# Hands_free_ControlUnit_V1.net
KiCad netlist of a schematic drawn in Altium Designer
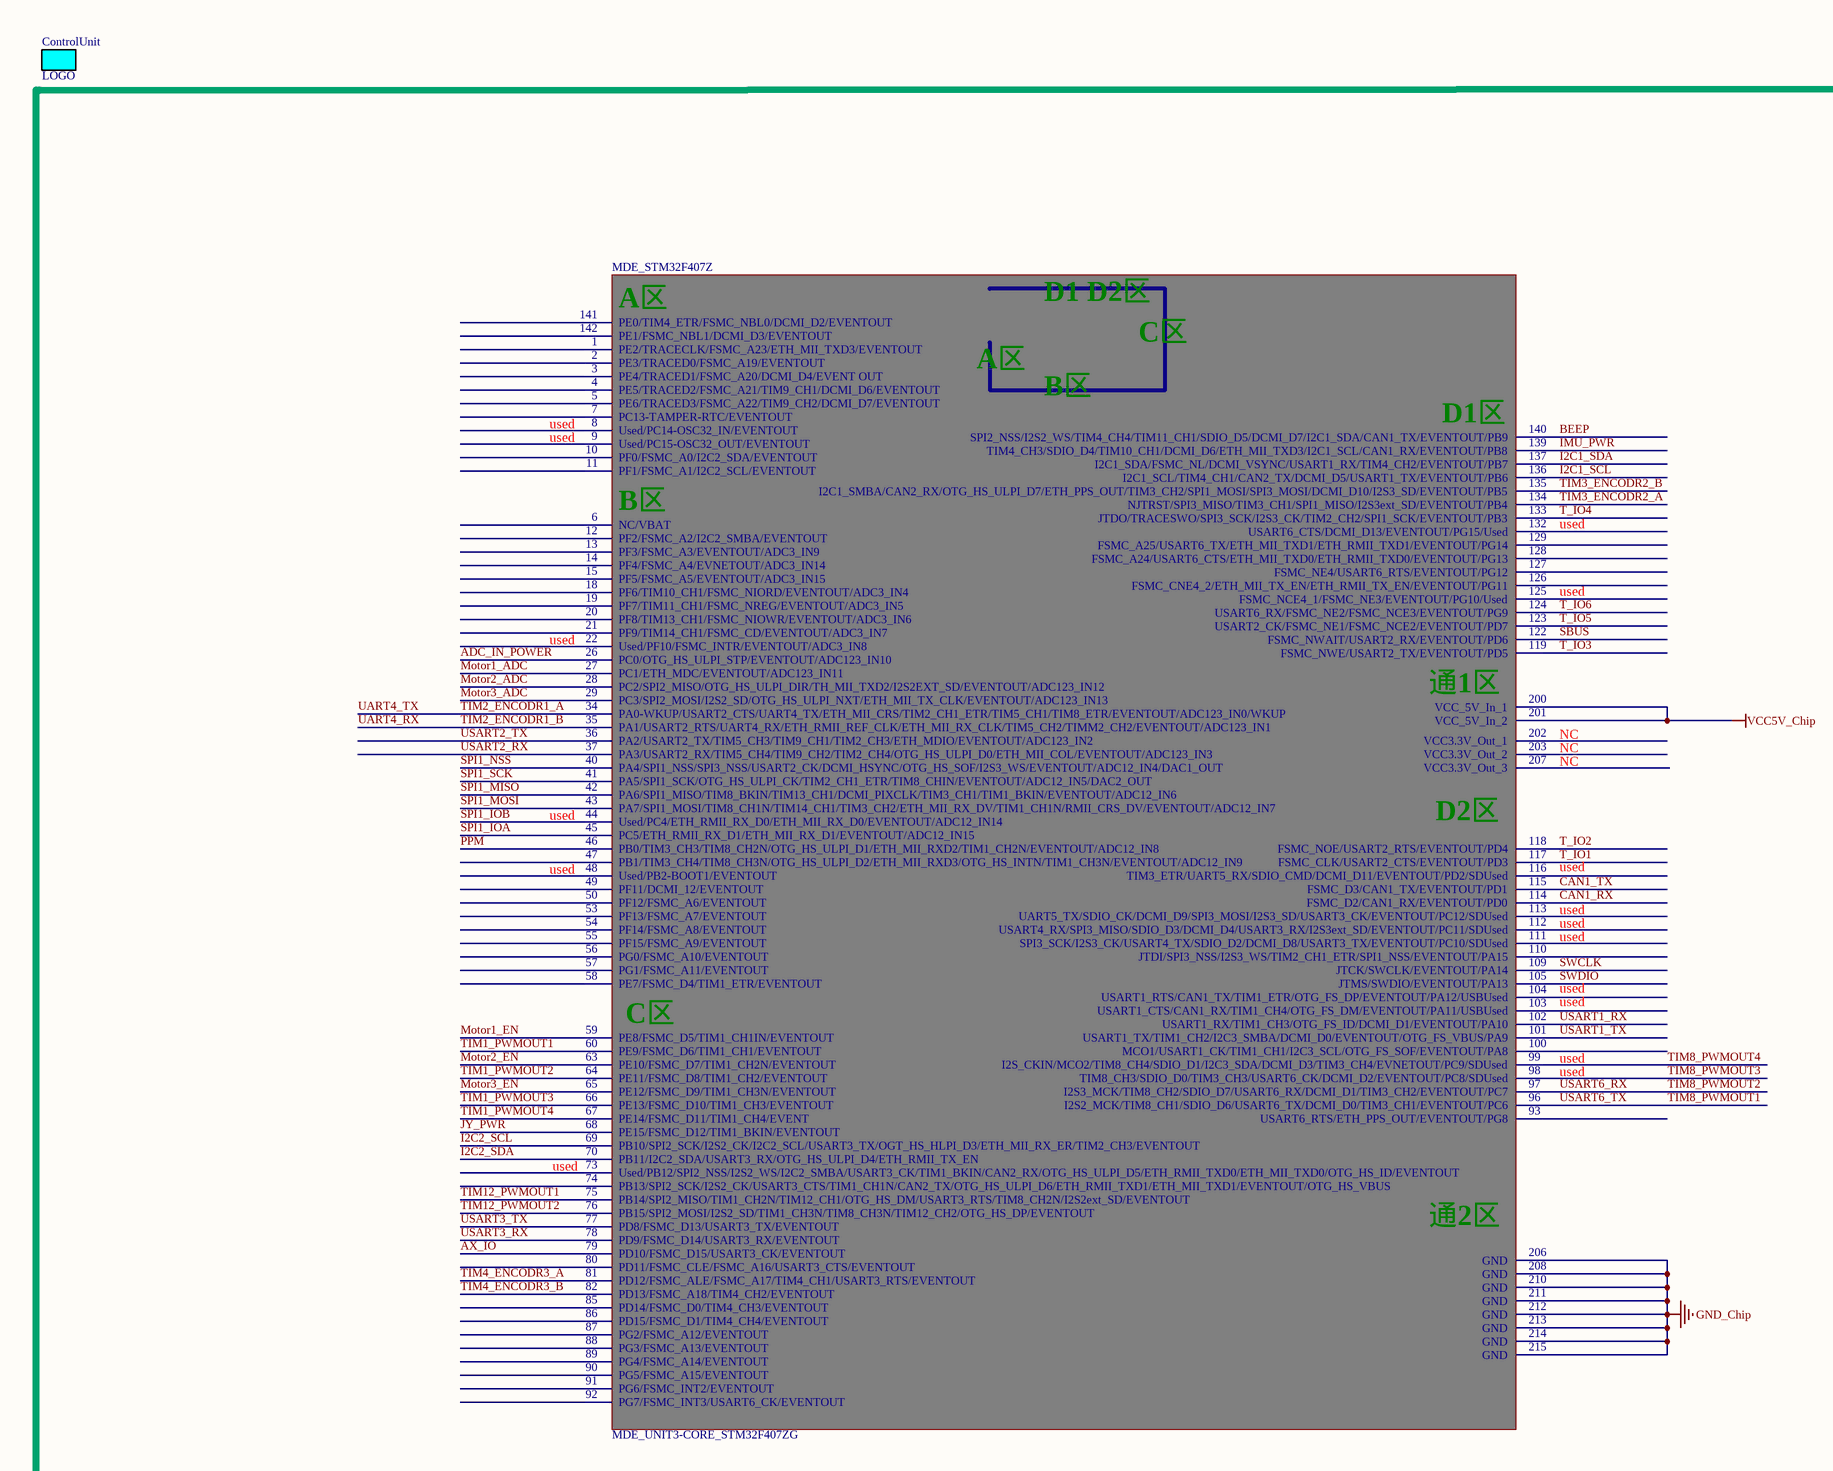
[diagram p0: Hands_free_ControlUnit_V1.SchDoc, top left]
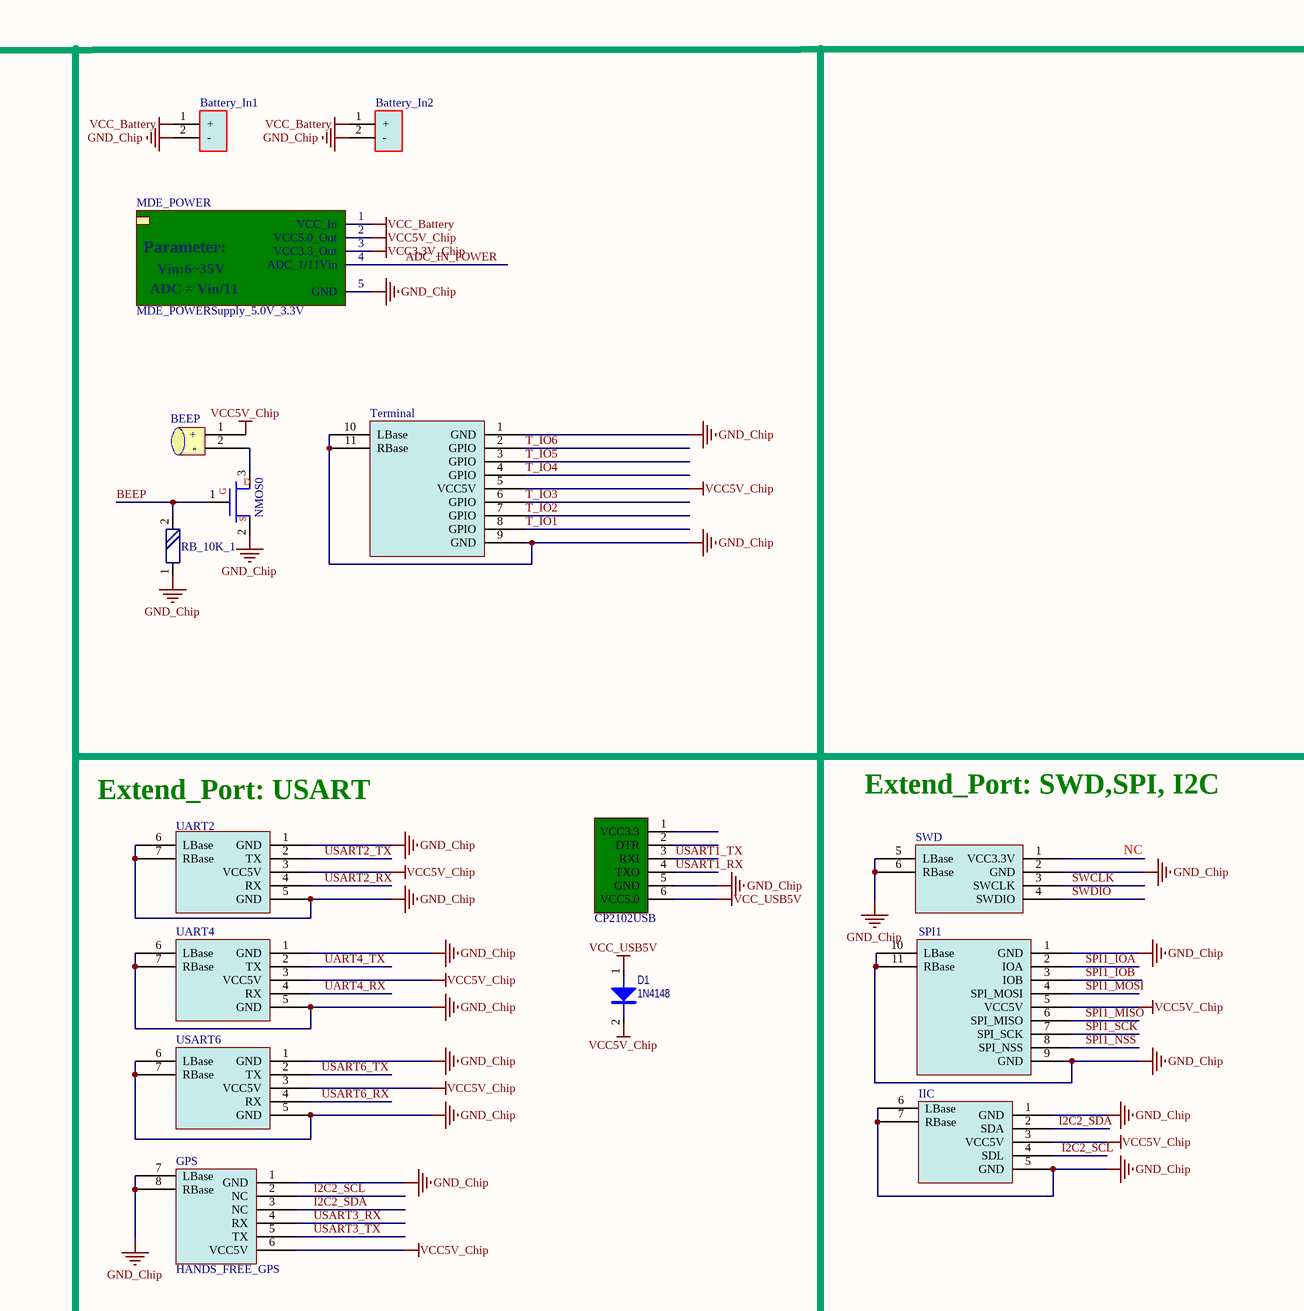
[diagram p1: Hands_free_ControlUnit_V1.SchDoc, top middle]
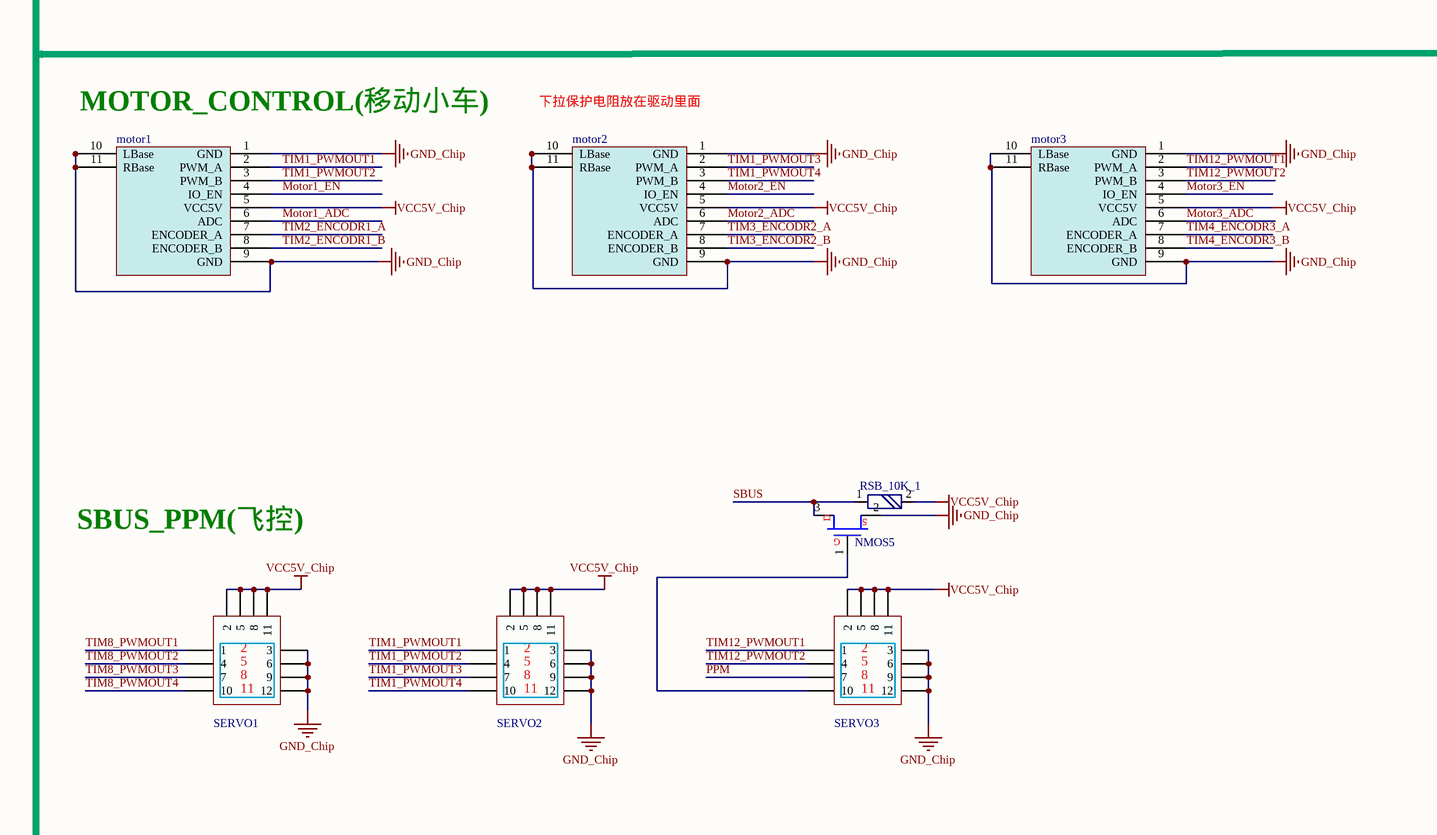
[diagram p2: Hands_free_ControlUnit_V1.SchDoc, bottom left]
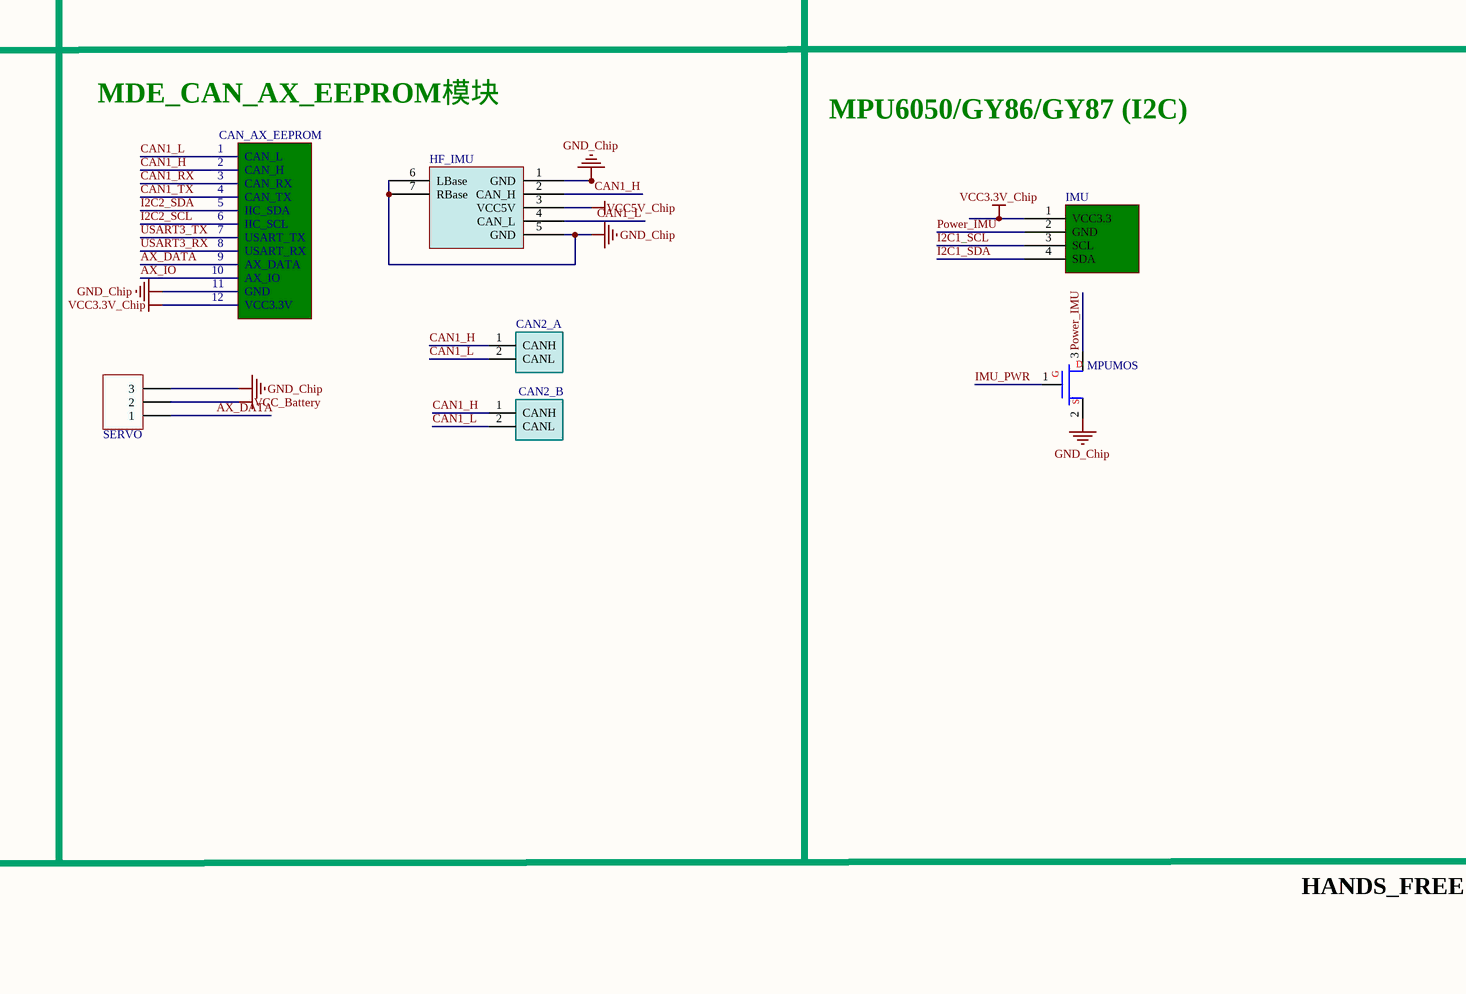
[diagram p3: Hands_free_ControlUnit_V1.SchDoc, bottom middle]
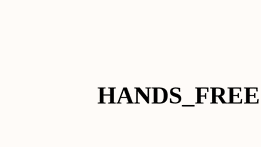
[diagram p4: Hands_free_ControlUnit_V1.SchDoc, bottom right]

(export (version "E")
  (design (tool "Eeschema 10.0.6"))
  (components
    (comp (ref "Battery_In1")
      (value "HDR_Header_Power_2P")
      (footprint "HDR_MOLEX_POWER5557_DH_2P")
      (libsource (lib "HANDS-FREEE-PcbLib-V1.00") (part "HDR_Header_Power_2P"))
    )
    (comp (ref "Battery_In2")
      (value "HDR_Header_Power_2P")
      (footprint "HDR_MOLEX_POWER5557_DH_2P")
      (libsource (lib "HANDS-FREEE-PcbLib-V1.00") (part "HDR_Header_Power_2P"))
    )
    (comp (ref "BEEP")
      (value "ELE_蜂鸣器12*X")
      (footprint "ELE_蜂鸣器_D_12*X")
      (libsource (lib "Hands_free") (part "ELE_蜂鸣器12*X"))
    )
    (comp (ref "CAN2_A")
      (value "HDR_HEADER_CAN_DH_2P")
      (footprint "HDR_MOLEX_CANMX3.0_DH_2P")
      (libsource (lib "Hands_free") (part "HDR_HEADER_CAN_DH_2P"))
    )
    (comp (ref "CAN2_B")
      (value "HDR_HEADER_CAN_DH_2P")
      (footprint "HDR_MOLEX_CANMX3.0_DH_2P")
      (libsource (lib "Hands_free") (part "HDR_HEADER_CAN_DH_2P"))
    )
    (comp (ref "CAN_AX_EEPROM")
      (value "MDE_CAN_AX_EEPROM")
      (footprint "MDE_CAN_AX_EEPROM")
      (libsource (lib "Hands_free") (part "MDE_CAN_AX_EEPROM"))
    )
    (comp (ref "ControlUnit") (value "LOGO") (footprint "LOGO") (libsource (lib "Hands_free") (part "LOGO")))
    (comp (ref "CP2102USB")
      (value "MDE_CP2102-TTLUSB")
      (footprint "MDE_CP2102-TTLUSB_BASE")
      (description "CP2102模块，TTL-USB")
      (libsource (lib "HANDS-FREEE-PcbLib-V1.06") (part "MDE_CP2102-TTLUSB"))
    )
    (comp (ref "D1")
      (value "1N4148")
      (footprint "ELE_D1206")
      (description "二极管")
      (libsource (lib "Hands_free") (part "ELE_Diode"))
    )
    (comp (ref "GPS")
      (value "HANDS_FREE_GPS")
      (footprint "HDR_Molex_PH_1.25_6P")
      (libsource (lib "Hands_free") (part "HANDS_FREE_GPS"))
    )
    (comp (ref "HF_IMU")
      (value "HANDS_FREE_IMU")
      (footprint "HDR_Molex_PH_1.25_5P")
      (libsource (lib "Hands_free") (part "HANDS_FREE_IMU"))
    )
    (comp (ref "IIC")
      (value "HANDS_FREE_IIC")
      (footprint "HDR_Molex_PH_1.25_5P")
      (libsource (lib "Hands_free") (part "HANDS_FREE_IIC"))
    )
    (comp (ref "IMU")
      (value "MDE_GY86_87")
      (footprint "MDE_GY86_GY87_BASE")
      (description "IMU模块")
      (libsource (lib "Hands_free") (part "MDE_GY86_87"))
    )
    (comp (ref "MDE_POWER")
      (value "MDE_POWERSupply_5.0V_3.3V")
      (footprint "MDE_POWERSupply_5.0V_3.3V")
      (libsource (lib "HANDS-FREEE-PcbLib-V1.06") (part "MDE_POWERSupply_5.0V_3.3V"))
    )
    (comp (ref "MDE_STM32F407Z")
      (value "MDE_UNIT3-CORE_STM32F407ZG")
      (footprint "MDE_UNIT3-CORE_STM32F407ZG")
      (libsource (lib "HANDS-FREEE-PcbLib-V1.05") (part "MDE_UNIT3-CORE_STM32F407ZG"))
    )
    (comp (ref "motor1")
      (value "*MOTOR")
      (footprint "HDR_Molex_PH_1.25_9P")
      (libsource (lib "Hands_free") (part "HANDS_FREE_MOTOR"))
    )
    (comp (ref "motor2")
      (value "*MOTOR")
      (footprint "HDR_Molex_PH_1.25_9P")
      (libsource (lib "Hands_free") (part "HANDS_FREE_MOTOR"))
    )
    (comp (ref "motor3")
      (value "*MOTOR")
      (footprint "HDR_Molex_PH_1.25_9P")
      (libsource (lib "Hands_free") (part "HANDS_FREE_MOTOR"))
    )
    (comp (ref "MPUMOS")
      (value "SIS412DN")
      (footprint "CHP_SOT23_P_3P")
      (description "MOS管")
      (fields (field (name "PUBLISHER") "Altium Limited"))
      (libsource (lib "Hands_free") (part "ELE_NMOS_1"))
    )
    (comp (ref "NMOS0")
      (value "SIS412DN")
      (footprint "CHP_SOT23_P_3P")
      (description "MOS管")
      (fields (field (name "PUBLISHER") "Altium Limited"))
      (libsource (lib "Hands_free") (part "ELE_NMOS_1"))
    )
    (comp (ref "NMOS5")
      (value "SIS412DN")
      (footprint "CHP_SOT23_P_3P")
      (description "MOS管")
      (fields (field (name "PUBLISHER") "Altium Limited"))
      (libsource (lib "Hands_free") (part "ELE_NMOS_1"))
    )
    (comp (ref "RB_10K_1")
      (value "ELE_RES_1")
      (footprint "ELE_0805_P")
      (description "电阻")
      (libsource (lib "Hands_free") (part "ELE_RES_1"))
    )
    (comp (ref "RSB_10K_1")
      (value "ELE_RES_1")
      (footprint "ELE_0805_P")
      (description "电阻")
      (libsource (lib "Hands_free") (part "ELE_RES_1"))
    )
    (comp (ref "SERVO")
      (value "HDR_Header_1*3")
      (footprint "HDR_数字舵机接口_D")
      (fields (field (name "PUBLISHER") "Altium Limited"))
      (libsource (lib "Hands_free") (part "HDR_Header_1*3"))
    )
    (comp (ref "SERVO1")
      (value "HDR_Header_4*3")
      (footprint "HDR_Header_3.00_DV_3*4")
      (libsource (lib "Hands_free") (part "HDR_Header_4*3"))
    )
    (comp (ref "SERVO2")
      (value "HDR_Header_4*3")
      (footprint "HDR_Header_3.00_DV_3*4")
      (libsource (lib "Hands_free") (part "HDR_Header_4*3"))
    )
    (comp (ref "SERVO3")
      (value "HDR_Header_4*3")
      (footprint "HDR_Header_3.00_DV_3*4")
      (libsource (lib "Hands_free") (part "HDR_Header_4*3"))
    )
    (comp (ref "SPI1")
      (value "HANDS_FREE_SPI")
      (footprint "HDR_Molex_PH_1.25_9P")
      (libsource (lib "Hands_free") (part "HANDS_FREE_SPI"))
    )
    (comp (ref "SWD")
      (value "HANDS_FREE_SWD")
      (footprint "HDR_Molex_PH_1.25_4P")
      (libsource (lib "Hands_free") (part "HANDS_FREE_SWD"))
    )
    (comp (ref "Terminal")
      (value "HANDS_FREE_TERMINAL")
      (footprint "HDR_Molex_PH_1.25_9P")
      (libsource (lib "Hands_free") (part "HANDS_FREE_TERMINAL"))
    )
    (comp (ref "UART2")
      (value "HANDS_FREE_USART")
      (footprint "HDR_Molex_PH_1.25_5P")
      (libsource (lib "Hands_free") (part "HANDS_FREE_USART"))
    )
    (comp (ref "UART4")
      (value "HANDS_FREE_USART")
      (footprint "HDR_Molex_PH_1.25_5P")
      (libsource (lib "Hands_free") (part "HANDS_FREE_USART"))
    )
    (comp (ref "USART6")
      (value "HANDS_FREE_USART")
      (footprint "HDR_Molex_PH_1.25_5P")
      (libsource (lib "Hands_free") (part "HANDS_FREE_USART"))
    )
  )
  (nets
    (net (code "1") (name "/ADC_IN_POWER") (class "Default")
      (node (ref "MDE_POWER") (pin "4") (pinfunction "ADC_1/11Vin_4") (pintype "passive"))
      (node (ref "MDE_STM32F407Z") (pin "26") (pinfunction "PC0/OTG_HS_ULPI_STP/EVENTOUT/ADC123_IN10_26") (pintype "passive"))
    )
    (net (code "2") (name "/AX_DATA") (class "Default")
      (node (ref "CAN_AX_EEPROM") (pin "9") (pinfunction "AX_DATA_9") (pintype "passive"))
      (node (ref "SERVO") (pin "1") (pinfunction "1_1") (pintype "passive"))
    )
    (net (code "3") (name "/AX_IO") (class "Default")
      (node (ref "CAN_AX_EEPROM") (pin "10") (pinfunction "AX_IO_10") (pintype "passive"))
      (node (ref "MDE_STM32F407Z") (pin "79") (pinfunction "PD10/FSMC_D15/USART3_CK/EVENTOUT_79") (pintype "passive"))
    )
    (net (code "4") (name "/BEEP") (class "Default")
      (node (ref "MDE_STM32F407Z") (pin "140") (pinfunction "SPI2_NSS/I2S2_WS/TIM4_CH4/TIM11_CH1/SDIO_D5/DCMI_D7/I2C1_SDA/CAN1_TX/EVENTOUT/PB9_140") (pintype "passive"))
      (node (ref "NMOS0") (pin "1") (pinfunction "G_1") (pintype "passive"))
      (node (ref "RB_10K_1") (pin "2") (pintype "passive"))
    )
    (net (code "5") (name "/CAN1_H") (class "Default")
      (node (ref "CAN2_A") (pin "1") (pinfunction "CANH_1") (pintype "passive"))
      (node (ref "CAN2_B") (pin "1") (pinfunction "CANH_1") (pintype "passive"))
      (node (ref "CAN_AX_EEPROM") (pin "2") (pinfunction "CAN_H_2") (pintype "passive"))
      (node (ref "HF_IMU") (pin "2") (pinfunction "CAN_H_2") (pintype "passive"))
    )
    (net (code "6") (name "/CAN1_L") (class "Default")
      (node (ref "CAN2_A") (pin "2") (pinfunction "CANL_2") (pintype "passive"))
      (node (ref "CAN2_B") (pin "2") (pinfunction "CANL_2") (pintype "passive"))
      (node (ref "CAN_AX_EEPROM") (pin "1") (pinfunction "CAN_L_1") (pintype "passive"))
      (node (ref "HF_IMU") (pin "4") (pinfunction "CAN_L_4") (pintype "passive"))
    )
    (net (code "7") (name "/CAN1_RX") (class "Default")
      (node (ref "CAN_AX_EEPROM") (pin "3") (pinfunction "CAN_RX_3") (pintype "passive"))
      (node (ref "MDE_STM32F407Z") (pin "114") (pinfunction "FSMC_D2/CAN1_RX/EVENTOUT/PD0_114") (pintype "passive"))
    )
    (net (code "8") (name "/CAN1_TX") (class "Default")
      (node (ref "CAN_AX_EEPROM") (pin "4") (pinfunction "CAN_TX_4") (pintype "passive"))
      (node (ref "MDE_STM32F407Z") (pin "115") (pinfunction "FSMC_D3/CAN1_TX/EVENTOUT/PD1_115") (pintype "passive"))
    )
    (net (code "9") (name "/I2C1_SCL") (class "Default")
      (node (ref "IMU") (pin "3") (pinfunction "SCL_3") (pintype "passive"))
      (node (ref "MDE_STM32F407Z") (pin "136") (pinfunction "I2C1_SCL/TIM4_CH1/CAN2_TX/DCMI_D5/USART1_TX/EVENTOUT/PB6_136") (pintype "passive"))
    )
    (net (code "10") (name "/I2C1_SDA") (class "Default")
      (node (ref "IMU") (pin "4") (pinfunction "SDA_4") (pintype "passive"))
      (node (ref "MDE_STM32F407Z") (pin "137") (pinfunction "I2C1_SDA/FSMC_NL/DCMI_VSYNC/USART1_RX/TIM4_CH2/EVENTOUT/PB7_137") (pintype "passive"))
    )
    (net (code "11") (name "/I2C2_SCL") (class "Default")
      (node (ref "CAN_AX_EEPROM") (pin "6") (pinfunction "IIC_SCL_6") (pintype "passive"))
      (node (ref "GPS") (pin "2") (pinfunction "NC_2") (pintype "passive"))
      (node (ref "IIC") (pin "4") (pinfunction "SDL_4") (pintype "passive"))
      (node (ref "MDE_STM32F407Z") (pin "69") (pinfunction "PB10/SPI2_SCK/I2S2_CK/I2C2_SCL/USART3_TX/OGT_HS_HLPI_D3/ETH_MII_RX_ER/TIM2_CH3/EVENTOUT_69") (pintype "passive"))
    )
    (net (code "12") (name "/I2C2_SDA") (class "Default")
      (node (ref "CAN_AX_EEPROM") (pin "5") (pinfunction "IIC_SDA_5") (pintype "passive"))
      (node (ref "GPS") (pin "3") (pinfunction "NC_3") (pintype "passive"))
      (node (ref "IIC") (pin "2") (pinfunction "SDA_2") (pintype "passive"))
      (node (ref "MDE_STM32F407Z") (pin "70") (pinfunction "PB11/I2C2_SDA/USART3_RX/OTG_HS_ULPI_D4/ETH_RMII_TX_EN_70") (pintype "passive"))
    )
    (net (code "13") (name "/IMU_PWR") (class "Default")
      (node (ref "MDE_STM32F407Z") (pin "139") (pinfunction "TIM4_CH3/SDIO_D4/TIM10_CH1/DCMI_D6/ETH_MII_TXD3/I2C1_SCL/CAN1_RX/EVENTOUT/PB8_139") (pintype "passive"))
      (node (ref "MPUMOS") (pin "1") (pinfunction "G_1") (pintype "passive"))
    )
    (net (code "14") (name "/JY_PWR") (class "Default")
      (node (ref "MDE_STM32F407Z") (pin "68") (pinfunction "PE15/FSMC_D12/TIM1_BKIN/EVENTOUT_68") (pintype "passive"))
    )
    (net (code "15") (name "/Motor1_ADC") (class "Default")
      (node (ref "MDE_STM32F407Z") (pin "27") (pinfunction "PC1/ETH_MDC/EVENTOUT/ADC123_IN11_27") (pintype "passive"))
      (node (ref "motor1") (pin "6") (pinfunction "ADC_6") (pintype "passive"))
    )
    (net (code "16") (name "/Motor1_EN") (class "Default")
      (node (ref "MDE_STM32F407Z") (pin "59") (pinfunction "PE8/FSMC_D5/TIM1_CH1IN/EVENTOUT_59") (pintype "passive"))
      (node (ref "motor1") (pin "4") (pinfunction "IO_EN_4") (pintype "passive"))
    )
    (net (code "17") (name "/Motor2_ADC") (class "Default")
      (node (ref "MDE_STM32F407Z") (pin "28") (pinfunction "PC2/SPI2_MISO/OTG_HS_ULPI_DIR/TH_MII_TXD2/I2S2EXT_SD/EVENTOUT/ADC123_IN12_28") (pintype "passive"))
      (node (ref "motor2") (pin "6") (pinfunction "ADC_6") (pintype "passive"))
    )
    (net (code "18") (name "/Motor2_EN") (class "Default")
      (node (ref "MDE_STM32F407Z") (pin "63") (pinfunction "PE10/FSMC_D7/TIM1_CH2N/EVENTOUT_63") (pintype "passive"))
      (node (ref "motor2") (pin "4") (pinfunction "IO_EN_4") (pintype "passive"))
    )
    (net (code "19") (name "/Motor3_ADC") (class "Default")
      (node (ref "MDE_STM32F407Z") (pin "29") (pinfunction "PC3/SPI2_MOSI/I2S2_SD/OTG_HS_ULPI_NXT/ETH_MII_TX_CLK/EVENTOUT/ADC123_IN13_29") (pintype "passive"))
      (node (ref "motor3") (pin "6") (pinfunction "ADC_6") (pintype "passive"))
    )
    (net (code "20") (name "/Motor3_EN") (class "Default")
      (node (ref "MDE_STM32F407Z") (pin "65") (pinfunction "PE12/FSMC_D9/TIM1_CH3N/EVENTOUT_65") (pintype "passive"))
      (node (ref "motor3") (pin "4") (pinfunction "IO_EN_4") (pintype "passive"))
    )
    (net (code "21") (name "/PPM") (class "Default")
      (node (ref "MDE_STM32F407Z") (pin "46") (pinfunction "PB0/TIM3_CH3/TIM8_CH2N/OTG_HS_ULPI_D1/ETH_MII_RXD2/TIM1_CH2N/EVENTOUT/ADC12_IN8_46") (pintype "passive"))
      (node (ref "SERVO3") (pin "7") (pinfunction "7_7") (pintype "passive"))
    )
    (net (code "22") (name "/Power_IMU") (class "Default")
      (node (ref "IMU") (pin "2") (pinfunction "GND_2") (pintype "passive"))
      (node (ref "MPUMOS") (pin "3") (pinfunction "D_3") (pintype "passive"))
    )
    (net (code "23") (name "/SBUS") (class "Default")
      (node (ref "MDE_STM32F407Z") (pin "122") (pinfunction "FSMC_NWAIT/USART2_RX/EVENTOUT/PD6_122") (pintype "passive"))
      (node (ref "NMOS5") (pin "3") (pinfunction "D_3") (pintype "passive"))
      (node (ref "RSB_10K_1") (pin "1") (pintype "passive"))
    )
    (net (code "24") (name "/SPI1_IOA") (class "Default")
      (node (ref "MDE_STM32F407Z") (pin "45") (pinfunction "PC5/ETH_RMII_RX_D1/ETH_MII_RX_D1/EVENTOUT/ADC12_IN15_45") (pintype "passive"))
      (node (ref "SPI1") (pin "2") (pinfunction "IOA_2") (pintype "passive"))
    )
    (net (code "25") (name "/SPI1_IOB") (class "Default")
      (node (ref "MDE_STM32F407Z") (pin "44") (pinfunction "Used/PC4/ETH_RMII_RX_D0/ETH_MII_RX_D0/EVENTOUT/ADC12_IN14_44") (pintype "passive"))
      (node (ref "SPI1") (pin "3") (pinfunction "IOB_3") (pintype "passive"))
    )
    (net (code "26") (name "/SPI1_MISO") (class "Default")
      (node (ref "MDE_STM32F407Z") (pin "42") (pinfunction "PA6/SPI1_MISO/TIM8_BKIN/TIM13_CH1/DCMI_PIXCLK/TIM3_CH1/TIM1_BKIN/EVENTOUT/ADC12_IN6_42") (pintype "passive"))
      (node (ref "SPI1") (pin "6") (pinfunction "SPI_MISO_6") (pintype "passive"))
    )
    (net (code "27") (name "/SPI1_MOSI") (class "Default")
      (node (ref "MDE_STM32F407Z") (pin "43") (pinfunction "PA7/SPI1_MOSI/TIM8_CH1N/TIM14_CH1/TIM3_CH2/ETH_MII_RX_DV/TIM1_CH1N/RMII_CRS_DV/EVENTOUT/ADC12_IN7_43") (pintype "passive"))
      (node (ref "SPI1") (pin "4") (pinfunction "SPI_MOSI_4") (pintype "passive"))
    )
    (net (code "28") (name "/SPI1_NSS") (class "Default")
      (node (ref "MDE_STM32F407Z") (pin "40") (pinfunction "PA4/SPI1_NSS/SPI3_NSS/USART2_CK/DCMI_HSYNC/OTG_HS_SOF/I2S3_WS/EVENTOUT/ADC12_IN4/DAC1_OUT_40") (pintype "passive"))
      (node (ref "SPI1") (pin "8") (pinfunction "SPI_NSS_8") (pintype "passive"))
    )
    (net (code "29") (name "/SPI1_SCK") (class "Default")
      (node (ref "MDE_STM32F407Z") (pin "41") (pinfunction "PA5/SPI1_SCK/OTG_HS_ULPI_CK/TIM2_CH1_ETR/TIM8_CHIN/EVENTOUT/ADC12_IN5/DAC2_OUT_41") (pintype "passive"))
      (node (ref "SPI1") (pin "7") (pinfunction "SPI_SCK_7") (pintype "passive"))
    )
    (net (code "30") (name "/SWCLK") (class "Default")
      (node (ref "MDE_STM32F407Z") (pin "109") (pinfunction "JTCK/SWCLK/EVENTOUT/PA14_109") (pintype "passive"))
      (node (ref "SWD") (pin "3") (pinfunction "SWCLK_3") (pintype "passive"))
    )
    (net (code "31") (name "/SWDIO") (class "Default")
      (node (ref "MDE_STM32F407Z") (pin "105") (pinfunction "JTMS/SWDIO/EVENTOUT/PA13_105") (pintype "passive"))
      (node (ref "SWD") (pin "4") (pinfunction "SWDIO_4") (pintype "passive"))
    )
    (net (code "32") (name "/TIM1_PWMOUT1") (class "Default")
      (node (ref "MDE_STM32F407Z") (pin "60") (pinfunction "PE9/FSMC_D6/TIM1_CH1/EVENTOUT_60") (pintype "passive"))
      (node (ref "SERVO2") (pin "1") (pinfunction "1_1") (pintype "passive"))
      (node (ref "motor1") (pin "2") (pinfunction "PWM_A_2") (pintype "passive"))
    )
    (net (code "33") (name "/TIM1_PWMOUT2") (class "Default")
      (node (ref "MDE_STM32F407Z") (pin "64") (pinfunction "PE11/FSMC_D8/TIM1_CH2/EVENTOUT_64") (pintype "passive"))
      (node (ref "SERVO2") (pin "4") (pinfunction "4_4") (pintype "passive"))
      (node (ref "motor1") (pin "3") (pinfunction "PWM_B_3") (pintype "passive"))
    )
    (net (code "34") (name "/TIM1_PWMOUT3") (class "Default")
      (node (ref "MDE_STM32F407Z") (pin "66") (pinfunction "PE13/FSMC_D10/TIM1_CH3/EVENTOUT_66") (pintype "passive"))
      (node (ref "SERVO2") (pin "7") (pinfunction "7_7") (pintype "passive"))
      (node (ref "motor2") (pin "2") (pinfunction "PWM_A_2") (pintype "passive"))
    )
    (net (code "35") (name "/TIM1_PWMOUT4") (class "Default")
      (node (ref "MDE_STM32F407Z") (pin "67") (pinfunction "PE14/FSMC_D11/TIM1_CH4/EVENT_67") (pintype "passive"))
      (node (ref "SERVO2") (pin "10") (pinfunction "10_10") (pintype "passive"))
      (node (ref "motor2") (pin "3") (pinfunction "PWM_B_3") (pintype "passive"))
    )
    (net (code "36") (name "/TIM2_ENCODR1_A") (class "Default")
      (node (ref "MDE_STM32F407Z") (pin "34") (pinfunction "PA0-WKUP/USART2_CTS/UART4_TX/ETH_MII_CRS/TIM2_CH1_ETR/TIM5_CH1/TIM8_ETR/EVENTOUT/ADC123_IN0/WKUP_34") (pintype "passive"))
      (node (ref "UART4") (pin "2") (pinfunction "TX_2") (pintype "passive"))
      (node (ref "motor1") (pin "7") (pinfunction "ENCODER_A_7") (pintype "passive"))
    )
    (net (code "37") (name "/TIM2_ENCODR1_B") (class "Default")
      (node (ref "MDE_STM32F407Z") (pin "35") (pinfunction "PA1/USART2_RTS/UART4_RX/ETH_RMII_REF_CLK/ETH_MII_RX_CLK/TIM5_CH2/TIMM2_CH2/EVENTOUT/ADC123_IN1_35") (pintype "passive"))
      (node (ref "UART4") (pin "4") (pinfunction "RX_4") (pintype "passive"))
      (node (ref "motor1") (pin "8") (pinfunction "ENCODER_B_8") (pintype "passive"))
    )
    (net (code "38") (name "/TIM3_ENCODR2_A") (class "Default")
      (node (ref "MDE_STM32F407Z") (pin "134") (pinfunction "NJTRST/SPI3_MISO/TIM3_CH1/SPI1_MISO/I2S3ext_SD/EVENTOUT/PB4_134") (pintype "passive"))
      (node (ref "motor2") (pin "7") (pinfunction "ENCODER_A_7") (pintype "passive"))
    )
    (net (code "39") (name "/TIM3_ENCODR2_B") (class "Default")
      (node (ref "MDE_STM32F407Z") (pin "135") (pinfunction "I2C1_SMBA/CAN2_RX/OTG_HS_ULPI_D7/ETH_PPS_OUT/TIM3_CH2/SPI1_MOSI/SPI3_MOSI/DCMI_D10/I2S3_SD/EVENTOUT/PB5_135") (pintype "passive"))
      (node (ref "motor2") (pin "8") (pinfunction "ENCODER_B_8") (pintype "passive"))
    )
    (net (code "40") (name "/TIM4_ENCODR3_A") (class "Default")
      (node (ref "MDE_STM32F407Z") (pin "81") (pinfunction "PD12/FSMC_ALE/FSMC_A17/TIM4_CH1/USART3_RTS/EVENTOUT_81") (pintype "passive"))
      (node (ref "motor3") (pin "7") (pinfunction "ENCODER_A_7") (pintype "passive"))
    )
    (net (code "41") (name "/TIM4_ENCODR3_B") (class "Default")
      (node (ref "MDE_STM32F407Z") (pin "82") (pinfunction "PD13/FSMC_A18/TIM4_CH2/EVENTOUT_82") (pintype "passive"))
      (node (ref "motor3") (pin "8") (pinfunction "ENCODER_B_8") (pintype "passive"))
    )
    (net (code "42") (name "/TIM8_PWMOUT1") (class "Default")
      (node (ref "MDE_STM32F407Z") (pin "96") (pinfunction "I2S2_MCK/TIM8_CH1/SDIO_D6/USART6_TX/DCMI_D0/TIM3_CH1/EVENTOUT/PC6_96") (pintype "passive"))
      (node (ref "SERVO1") (pin "1") (pinfunction "1_1") (pintype "passive"))
      (node (ref "USART6") (pin "2") (pinfunction "TX_2") (pintype "passive"))
    )
    (net (code "43") (name "/TIM8_PWMOUT2") (class "Default")
      (node (ref "MDE_STM32F407Z") (pin "97") (pinfunction "I2S3_MCK/TIM8_CH2/SDIO_D7/USART6_RX/DCMI_D1/TIM3_CH2/EVENTOUT/PC7_97") (pintype "passive"))
      (node (ref "SERVO1") (pin "4") (pinfunction "4_4") (pintype "passive"))
      (node (ref "USART6") (pin "4") (pinfunction "RX_4") (pintype "passive"))
    )
    (net (code "44") (name "/TIM8_PWMOUT3") (class "Default")
      (node (ref "MDE_STM32F407Z") (pin "98") (pinfunction "TIM8_CH3/SDIO_D0/TIM3_CH3/USART6_CK/DCMI_D2/EVENTOUT/PC8/SDUsed_98") (pintype "passive"))
      (node (ref "SERVO1") (pin "7") (pinfunction "7_7") (pintype "passive"))
    )
    (net (code "45") (name "/TIM8_PWMOUT4") (class "Default")
      (node (ref "MDE_STM32F407Z") (pin "99") (pinfunction "I2S_CKIN/MCO2/TIM8_CH4/SDIO_D1/I2C3_SDA/DCMI_D3/TIM3_CH4/EVNETOUT/PC9/SDUsed_99") (pintype "passive"))
      (node (ref "SERVO1") (pin "10") (pinfunction "10_10") (pintype "passive"))
    )
    (net (code "46") (name "/TIM12_PWMOUT1") (class "Default")
      (node (ref "MDE_STM32F407Z") (pin "75") (pinfunction "PB14/SPI2_MISO/TIM1_CH2N/TIM12_CH1/OTG_HS_DM/USART3_RTS/TIM8_CH2N/I2S2ext_SD/EVENTOUT_75") (pintype "passive"))
      (node (ref "SERVO3") (pin "1") (pinfunction "1_1") (pintype "passive"))
      (node (ref "motor3") (pin "2") (pinfunction "PWM_A_2") (pintype "passive"))
    )
    (net (code "47") (name "/TIM12_PWMOUT2") (class "Default")
      (node (ref "MDE_STM32F407Z") (pin "76") (pinfunction "PB15/SPI2_MOSI/I2S2_SD/TIM1_CH3N/TIM8_CH3N/TIM12_CH2/OTG_HS_DP/EVENTOUT_76") (pintype "passive"))
      (node (ref "SERVO3") (pin "4") (pinfunction "4_4") (pintype "passive"))
      (node (ref "motor3") (pin "3") (pinfunction "PWM_B_3") (pintype "passive"))
    )
    (net (code "48") (name "/T_IO1") (class "Default")
      (node (ref "MDE_STM32F407Z") (pin "117") (pinfunction "FSMC_CLK/USART2_CTS/EVENTOUT/PD3_117") (pintype "passive"))
      (node (ref "Terminal") (pin "8") (pinfunction "GPIO_8") (pintype "passive"))
    )
    (net (code "49") (name "/T_IO2") (class "Default")
      (node (ref "MDE_STM32F407Z") (pin "118") (pinfunction "FSMC_NOE/USART2_RTS/EVENTOUT/PD4_118") (pintype "passive"))
      (node (ref "Terminal") (pin "7") (pinfunction "GPIO_7") (pintype "passive"))
    )
    (net (code "50") (name "/T_IO3") (class "Default")
      (node (ref "MDE_STM32F407Z") (pin "119") (pinfunction "FSMC_NWE/USART2_TX/EVENTOUT/PD5_119") (pintype "passive"))
      (node (ref "Terminal") (pin "6") (pinfunction "GPIO_6") (pintype "passive"))
    )
    (net (code "51") (name "/T_IO4") (class "Default")
      (node (ref "MDE_STM32F407Z") (pin "133") (pinfunction "JTDO/TRACESWO/SPI3_SCK/I2S3_CK/TIM2_CH2/SPI1_SCK/EVENTOUT/PB3_133") (pintype "passive"))
      (node (ref "Terminal") (pin "4") (pinfunction "GPIO_4") (pintype "passive"))
    )
    (net (code "52") (name "/T_IO5") (class "Default")
      (node (ref "MDE_STM32F407Z") (pin "123") (pinfunction "USART2_CK/FSMC_NE1/FSMC_NCE2/EVENTOUT/PD7_123") (pintype "passive"))
      (node (ref "Terminal") (pin "3") (pinfunction "GPIO_3") (pintype "passive"))
    )
    (net (code "53") (name "/T_IO6") (class "Default")
      (node (ref "MDE_STM32F407Z") (pin "124") (pinfunction "USART6_RX/FSMC_NE2/FSMC_NCE3/EVENTOUT/PG9_124") (pintype "passive"))
      (node (ref "Terminal") (pin "2") (pinfunction "GPIO_2") (pintype "passive"))
    )
    (net (code "54") (name "/USART1_RX") (class "Default")
      (node (ref "CP2102USB") (pin "4") (pinfunction "TXO_4") (pintype "passive"))
      (node (ref "MDE_STM32F407Z") (pin "102") (pinfunction "USART1_RX/TIM1_CH3/OTG_FS_ID/DCMI_D1/EVENTOUT/PA10_102") (pintype "passive"))
    )
    (net (code "55") (name "/USART1_TX") (class "Default")
      (node (ref "CP2102USB") (pin "3") (pinfunction "RXI_3") (pintype "passive"))
      (node (ref "MDE_STM32F407Z") (pin "101") (pinfunction "USART1_TX/TIM1_CH2/I2C3_SMBA/DCMI_D0/EVENTOUT/OTG_FS_VBUS/PA9_101") (pintype "passive"))
    )
    (net (code "56") (name "/USART2_RX") (class "Default")
      (node (ref "MDE_STM32F407Z") (pin "37") (pinfunction "PA3/USART2_RX/TIM5_CH4/TIM9_CH2/TIM2_CH4/OTG_HS_ULPI_D0/ETH_MII_COL/EVENTOUT/ADC123_IN3_37") (pintype "passive"))
      (node (ref "UART2") (pin "4") (pinfunction "RX_4") (pintype "passive"))
    )
    (net (code "57") (name "/USART2_TX") (class "Default")
      (node (ref "MDE_STM32F407Z") (pin "36") (pinfunction "PA2/USART2_TX/TIM5_CH3/TIM9_CH1/TIM2_CH3/ETH_MDIO/EVENTOUT/ADC123_IN2_36") (pintype "passive"))
      (node (ref "UART2") (pin "2") (pinfunction "TX_2") (pintype "passive"))
    )
    (net (code "58") (name "/USART3_RX") (class "Default")
      (node (ref "CAN_AX_EEPROM") (pin "8") (pinfunction "USART_RX_8") (pintype "passive"))
      (node (ref "GPS") (pin "4") (pinfunction "RX_4") (pintype "passive"))
      (node (ref "MDE_STM32F407Z") (pin "78") (pinfunction "PD9/FSMC_D14/USART3_RX/EVENTOUT_78") (pintype "passive"))
    )
    (net (code "59") (name "/USART3_TX") (class "Default")
      (node (ref "CAN_AX_EEPROM") (pin "7") (pinfunction "USART_TX_7") (pintype "passive"))
      (node (ref "GPS") (pin "5") (pinfunction "TX_5") (pintype "passive"))
      (node (ref "MDE_STM32F407Z") (pin "77") (pinfunction "PD8/FSMC_D13/USART3_TX/EVENTOUT_77") (pintype "passive"))
    )
    (net (code "60") (name "GND_Chip") (class "Default")
      (node (ref "Battery_In1") (pin "2") (pinfunction "-_2") (pintype "passive"))
      (node (ref "Battery_In2") (pin "2") (pinfunction "-_2") (pintype "passive"))
      (node (ref "CAN_AX_EEPROM") (pin "11") (pinfunction "GND_11") (pintype "passive"))
      (node (ref "CP2102USB") (pin "5") (pinfunction "GND_5") (pintype "passive"))
      (node (ref "GPS") (pin "1") (pinfunction "GND_1") (pintype "passive"))
      (node (ref "GPS") (pin "7") (pinfunction "LBase_7") (pintype "passive"))
      (node (ref "GPS") (pin "8") (pinfunction "RBase_8") (pintype "passive"))
      (node (ref "HF_IMU") (pin "1") (pinfunction "GND_1") (pintype "passive"))
      (node (ref "HF_IMU") (pin "5") (pinfunction "GND_5") (pintype "passive"))
      (node (ref "HF_IMU") (pin "6") (pinfunction "LBase_6") (pintype "passive"))
      (node (ref "HF_IMU") (pin "7") (pinfunction "RBase_7") (pintype "passive"))
      (node (ref "IIC") (pin "1") (pinfunction "GND_1") (pintype "passive"))
      (node (ref "IIC") (pin "5") (pinfunction "GND_5") (pintype "passive"))
      (node (ref "IIC") (pin "6") (pinfunction "LBase_6") (pintype "passive"))
      (node (ref "IIC") (pin "7") (pinfunction "RBase_7") (pintype "passive"))
      (node (ref "MDE_POWER") (pin "5") (pinfunction "GND_5") (pintype "passive"))
      (node (ref "MDE_STM32F407Z") (pin "206") (pinfunction "GND_206") (pintype "passive"))
      (node (ref "MDE_STM32F407Z") (pin "208") (pinfunction "GND_208") (pintype "passive"))
      (node (ref "MDE_STM32F407Z") (pin "210") (pinfunction "GND_210") (pintype "passive"))
      (node (ref "MDE_STM32F407Z") (pin "211") (pinfunction "GND_211") (pintype "passive"))
      (node (ref "MDE_STM32F407Z") (pin "212") (pinfunction "GND_212") (pintype "passive"))
      (node (ref "MDE_STM32F407Z") (pin "213") (pinfunction "GND_213") (pintype "passive"))
      (node (ref "MDE_STM32F407Z") (pin "214") (pinfunction "GND_214") (pintype "passive"))
      (node (ref "MDE_STM32F407Z") (pin "215") (pinfunction "GND_215") (pintype "passive"))
      (node (ref "MPUMOS") (pin "2") (pinfunction "S_2") (pintype "passive"))
      (node (ref "NMOS0") (pin "2") (pinfunction "S_2") (pintype "passive"))
      (node (ref "NMOS5") (pin "2") (pinfunction "S_2") (pintype "passive"))
      (node (ref "RB_10K_1") (pin "1") (pintype "passive"))
      (node (ref "SERVO") (pin "3") (pinfunction "3_3") (pintype "passive"))
      (node (ref "SERVO1") (pin "12") (pinfunction "12_12") (pintype "passive"))
      (node (ref "SERVO1") (pin "3") (pinfunction "3_3") (pintype "passive"))
      (node (ref "SERVO1") (pin "6") (pinfunction "6_6") (pintype "passive"))
      (node (ref "SERVO1") (pin "9") (pinfunction "9_9") (pintype "passive"))
      (node (ref "SERVO2") (pin "12") (pinfunction "12_12") (pintype "passive"))
      (node (ref "SERVO2") (pin "3") (pinfunction "3_3") (pintype "passive"))
      (node (ref "SERVO2") (pin "6") (pinfunction "6_6") (pintype "passive"))
      (node (ref "SERVO2") (pin "9") (pinfunction "9_9") (pintype "passive"))
      (node (ref "SERVO3") (pin "12") (pinfunction "12_12") (pintype "passive"))
      (node (ref "SERVO3") (pin "3") (pinfunction "3_3") (pintype "passive"))
      (node (ref "SERVO3") (pin "6") (pinfunction "6_6") (pintype "passive"))
      (node (ref "SERVO3") (pin "9") (pinfunction "9_9") (pintype "passive"))
      (node (ref "SPI1") (pin "1") (pinfunction "GND_1") (pintype "passive"))
      (node (ref "SPI1") (pin "10") (pinfunction "LBase_10") (pintype "passive"))
      (node (ref "SPI1") (pin "11") (pinfunction "RBase_11") (pintype "passive"))
      (node (ref "SPI1") (pin "9") (pinfunction "GND_9") (pintype "passive"))
      (node (ref "SWD") (pin "2") (pinfunction "GND_2") (pintype "passive"))
      (node (ref "SWD") (pin "5") (pinfunction "LBase_5") (pintype "passive"))
      (node (ref "SWD") (pin "6") (pinfunction "RBase_6") (pintype "passive"))
      (node (ref "Terminal") (pin "1") (pinfunction "GND_1") (pintype "passive"))
      (node (ref "Terminal") (pin "10") (pinfunction "LBase_10") (pintype "passive"))
      (node (ref "Terminal") (pin "11") (pinfunction "RBase_11") (pintype "passive"))
      (node (ref "Terminal") (pin "9") (pinfunction "GND_9") (pintype "passive"))
      (node (ref "UART2") (pin "1") (pinfunction "GND_1") (pintype "passive"))
      (node (ref "UART2") (pin "5") (pinfunction "GND_5") (pintype "passive"))
      (node (ref "UART2") (pin "6") (pinfunction "LBase_6") (pintype "passive"))
      (node (ref "UART2") (pin "7") (pinfunction "RBase_7") (pintype "passive"))
      (node (ref "UART4") (pin "1") (pinfunction "GND_1") (pintype "passive"))
      (node (ref "UART4") (pin "5") (pinfunction "GND_5") (pintype "passive"))
      (node (ref "UART4") (pin "6") (pinfunction "LBase_6") (pintype "passive"))
      (node (ref "UART4") (pin "7") (pinfunction "RBase_7") (pintype "passive"))
      (node (ref "USART6") (pin "1") (pinfunction "GND_1") (pintype "passive"))
      (node (ref "USART6") (pin "5") (pinfunction "GND_5") (pintype "passive"))
      (node (ref "USART6") (pin "6") (pinfunction "LBase_6") (pintype "passive"))
      (node (ref "USART6") (pin "7") (pinfunction "RBase_7") (pintype "passive"))
      (node (ref "motor1") (pin "1") (pinfunction "GND_1") (pintype "passive"))
      (node (ref "motor1") (pin "10") (pinfunction "LBase_10") (pintype "passive"))
      (node (ref "motor1") (pin "11") (pinfunction "RBase_11") (pintype "passive"))
      (node (ref "motor1") (pin "9") (pinfunction "GND_9") (pintype "passive"))
      (node (ref "motor2") (pin "1") (pinfunction "GND_1") (pintype "passive"))
      (node (ref "motor2") (pin "10") (pinfunction "LBase_10") (pintype "passive"))
      (node (ref "motor2") (pin "11") (pinfunction "RBase_11") (pintype "passive"))
      (node (ref "motor2") (pin "9") (pinfunction "GND_9") (pintype "passive"))
      (node (ref "motor3") (pin "1") (pinfunction "GND_1") (pintype "passive"))
      (node (ref "motor3") (pin "10") (pinfunction "LBase_10") (pintype "passive"))
      (node (ref "motor3") (pin "11") (pinfunction "RBase_11") (pintype "passive"))
      (node (ref "motor3") (pin "9") (pinfunction "GND_9") (pintype "passive"))
    )
    (net (code "61") (name "Net-(BEEP--)") (class "Default")
      (node (ref "BEEP") (pin "2") (pinfunction "-_2") (pintype "passive"))
      (node (ref "NMOS0") (pin "3") (pinfunction "D_3") (pintype "passive"))
    )
    (net (code "62") (name "Net-(NMOS5-G)") (class "Default")
      (node (ref "NMOS5") (pin "1") (pinfunction "G_1") (pintype "passive"))
      (node (ref "SERVO3") (pin "10") (pinfunction "10_10") (pintype "passive"))
    )
    (net (code "63") (name "VCC3.3V_Chip") (class "Default")
      (node (ref "CAN_AX_EEPROM") (pin "12") (pinfunction "VCC3.3V_12") (pintype "passive"))
      (node (ref "IMU") (pin "1") (pinfunction "VCC3.3_1") (pintype "passive"))
      (node (ref "MDE_POWER") (pin "3") (pinfunction "VCC3.3_Out_3") (pintype "passive"))
    )
    (net (code "64") (name "VCC5V_Chip") (class "Default")
      (node (ref "BEEP") (pin "1") (pinfunction "+_1") (pintype "passive"))
      (node (ref "D1") (pin "2") (pintype "passive"))
      (node (ref "GPS") (pin "6") (pinfunction "VCC5V_6") (pintype "passive"))
      (node (ref "HF_IMU") (pin "3") (pinfunction "VCC5V_3") (pintype "passive"))
      (node (ref "IIC") (pin "3") (pinfunction "VCC5V_3") (pintype "passive"))
      (node (ref "MDE_POWER") (pin "2") (pinfunction "VCC5.0_Out_2") (pintype "passive"))
      (node (ref "MDE_STM32F407Z") (pin "200") (pinfunction "VCC_5V_In_1_200") (pintype "passive"))
      (node (ref "MDE_STM32F407Z") (pin "201") (pinfunction "VCC_5V_In_2_201") (pintype "passive"))
      (node (ref "RSB_10K_1") (pin "2") (pintype "passive"))
      (node (ref "SERVO1") (pin "11") (pinfunction "11_11") (pintype "passive"))
      (node (ref "SERVO1") (pin "2") (pinfunction "2_2") (pintype "passive"))
      (node (ref "SERVO1") (pin "5") (pinfunction "5_5") (pintype "passive"))
      (node (ref "SERVO1") (pin "8") (pinfunction "8_8") (pintype "passive"))
      (node (ref "SERVO2") (pin "11") (pinfunction "11_11") (pintype "passive"))
      (node (ref "SERVO2") (pin "2") (pinfunction "2_2") (pintype "passive"))
      (node (ref "SERVO2") (pin "5") (pinfunction "5_5") (pintype "passive"))
      (node (ref "SERVO2") (pin "8") (pinfunction "8_8") (pintype "passive"))
      (node (ref "SERVO3") (pin "11") (pinfunction "11_11") (pintype "passive"))
      (node (ref "SERVO3") (pin "2") (pinfunction "2_2") (pintype "passive"))
      (node (ref "SERVO3") (pin "5") (pinfunction "5_5") (pintype "passive"))
      (node (ref "SERVO3") (pin "8") (pinfunction "8_8") (pintype "passive"))
      (node (ref "SPI1") (pin "5") (pinfunction "VCC5V_5") (pintype "passive"))
      (node (ref "Terminal") (pin "5") (pinfunction "VCC5V_5") (pintype "passive"))
      (node (ref "UART2") (pin "3") (pinfunction "VCC5V_3") (pintype "passive"))
      (node (ref "UART4") (pin "3") (pinfunction "VCC5V_3") (pintype "passive"))
      (node (ref "USART6") (pin "3") (pinfunction "VCC5V_3") (pintype "passive"))
      (node (ref "motor1") (pin "5") (pinfunction "VCC5V_5") (pintype "passive"))
      (node (ref "motor2") (pin "5") (pinfunction "VCC5V_5") (pintype "passive"))
      (node (ref "motor3") (pin "5") (pinfunction "VCC5V_5") (pintype "passive"))
    )
    (net (code "65") (name "VCC_Battery") (class "Default")
      (node (ref "Battery_In1") (pin "1") (pinfunction "+_1") (pintype "passive"))
      (node (ref "Battery_In2") (pin "1") (pinfunction "+_1") (pintype "passive"))
      (node (ref "MDE_POWER") (pin "1") (pinfunction "VCC_In_1") (pintype "passive"))
      (node (ref "SERVO") (pin "2") (pinfunction "2_2") (pintype "passive"))
    )
    (net (code "66") (name "VCC_USB5V") (class "Default")
      (node (ref "CP2102USB") (pin "6") (pinfunction "VCC5.0_6") (pintype "passive"))
      (node (ref "D1") (pin "1") (pintype "passive"))
    )
    (net (code "67") (name "unconnected-(CP2102USB-DTR-Pad2)") (class "Default")
      (node (ref "CP2102USB") (pin "2") (pinfunction "DTR_2") (pintype "passive"))
    )
    (net (code "68") (name "unconnected-(CP2102USB-VCC3.3-Pad1)") (class "Default")
      (node (ref "CP2102USB") (pin "1") (pinfunction "VCC3.3_1") (pintype "passive"))
    )
    (net (code "69") (name "unconnected-(MDE_STM32F407Z-FSMC_A24{slash}USART6_CTS{slash}ETH_MII_TXD0{slash}ETH_RMII_TXD0{slash}EVENTOUT{slash}PG13-Pad128)") (class "Default")
      (node (ref "MDE_STM32F407Z") (pin "128") (pinfunction "FSMC_A24/USART6_CTS/ETH_MII_TXD0/ETH_RMII_TXD0/EVENTOUT/PG13_128") (pintype "passive"))
    )
    (net (code "70") (name "unconnected-(MDE_STM32F407Z-FSMC_A25{slash}USART6_TX{slash}ETH_MII_TXD1{slash}ETH_RMII_TXD1{slash}EVENTOUT{slash}PG14-Pad129)") (class "Default")
      (node (ref "MDE_STM32F407Z") (pin "129") (pinfunction "FSMC_A25/USART6_TX/ETH_MII_TXD1/ETH_RMII_TXD1/EVENTOUT/PG14_129") (pintype "passive"))
    )
    (net (code "71") (name "unconnected-(MDE_STM32F407Z-FSMC_CNE4_2{slash}ETH_MII_TX_EN{slash}ETH_RMII_TX_EN{slash}EVENTOUT{slash}PG11-Pad126)") (class "Default")
      (node (ref "MDE_STM32F407Z") (pin "126") (pinfunction "FSMC_CNE4_2/ETH_MII_TX_EN/ETH_RMII_TX_EN/EVENTOUT/PG11_126") (pintype "passive"))
    )
    (net (code "72") (name "unconnected-(MDE_STM32F407Z-FSMC_NCE4_1{slash}FSMC_NE3{slash}EVENTOUT{slash}PG10{slash}Used-Pad125)") (class "Default")
      (node (ref "MDE_STM32F407Z") (pin "125") (pinfunction "FSMC_NCE4_1/FSMC_NE3/EVENTOUT/PG10/Used_125") (pintype "passive"))
    )
    (net (code "73") (name "unconnected-(MDE_STM32F407Z-FSMC_NE4{slash}USART6_RTS{slash}EVENTOUT{slash}PG12-Pad127)") (class "Default")
      (node (ref "MDE_STM32F407Z") (pin "127") (pinfunction "FSMC_NE4/USART6_RTS/EVENTOUT/PG12_127") (pintype "passive"))
    )
    (net (code "74") (name "unconnected-(MDE_STM32F407Z-JTDI{slash}SPI3_NSS{slash}I2S3_WS{slash}TIM2_CH1_ETR{slash}SPI1_NSS{slash}EVENTOUT{slash}PA15-Pad110)") (class "Default")
      (node (ref "MDE_STM32F407Z") (pin "110") (pinfunction "JTDI/SPI3_NSS/I2S3_WS/TIM2_CH1_ETR/SPI1_NSS/EVENTOUT/PA15_110") (pintype "passive"))
    )
    (net (code "75") (name "unconnected-(MDE_STM32F407Z-MCO1{slash}USART1_CK{slash}TIM1_CH1{slash}I2C3_SCL{slash}OTG_FS_SOF{slash}EVENTOUT{slash}PA8-Pad100)") (class "Default")
      (node (ref "MDE_STM32F407Z") (pin "100") (pinfunction "MCO1/USART1_CK/TIM1_CH1/I2C3_SCL/OTG_FS_SOF/EVENTOUT/PA8_100") (pintype "passive"))
    )
    (net (code "76") (name "unconnected-(MDE_STM32F407Z-NC{slash}VBAT-Pad6)") (class "Default")
      (node (ref "MDE_STM32F407Z") (pin "6") (pinfunction "NC/VBAT_6") (pintype "passive"))
    )
    (net (code "77") (name "unconnected-(MDE_STM32F407Z-PB1{slash}TIM3_CH4{slash}TIM8_CH3N{slash}OTG_HS_ULPI_D2{slash}ETH_MII_RXD3{slash}OTG_HS_INTN{slash}TIM1_CH3N{slash}EVENTOUT{slash}ADC12_IN9-Pad47)") (class "Default")
      (node (ref "MDE_STM32F407Z") (pin "47") (pinfunction "PB1/TIM3_CH4/TIM8_CH3N/OTG_HS_ULPI_D2/ETH_MII_RXD3/OTG_HS_INTN/TIM1_CH3N/EVENTOUT/ADC12_IN9_47") (pintype "passive"))
    )
    (net (code "78") (name "unconnected-(MDE_STM32F407Z-PB13{slash}SPI2_SCK{slash}I2S2_CK{slash}USART3_CTS{slash}TIM1_CH1N{slash}CAN2_TX{slash}OTG_HS_ULPI_D6{slash}ETH_RMII_TXD1{slash}ETH_MII_TXD1{slash}EVENTOUT{slash}OTG_HS_VBUS-Pad74)") (class "Default")
      (node (ref "MDE_STM32F407Z") (pin "74") (pinfunction "PB13/SPI2_SCK/I2S2_CK/USART3_CTS/TIM1_CH1N/CAN2_TX/OTG_HS_ULPI_D6/ETH_RMII_TXD1/ETH_MII_TXD1/EVENTOUT/OTG_HS_VBUS_74") (pintype "passive"))
    )
    (net (code "79") (name "unconnected-(MDE_STM32F407Z-PC13-TAMPER-RTC{slash}EVENTOUT-Pad7)") (class "Default")
      (node (ref "MDE_STM32F407Z") (pin "7") (pinfunction "PC13-TAMPER-RTC/EVENTOUT_7") (pintype "passive"))
    )
    (net (code "80") (name "unconnected-(MDE_STM32F407Z-PD11{slash}FSMC_CLE{slash}FSMC_A16{slash}USART3_CTS{slash}EVENTOUT-Pad80)") (class "Default")
      (node (ref "MDE_STM32F407Z") (pin "80") (pinfunction "PD11/FSMC_CLE/FSMC_A16/USART3_CTS/EVENTOUT_80") (pintype "passive"))
    )
    (net (code "81") (name "unconnected-(MDE_STM32F407Z-PD14{slash}FSMC_D0{slash}TIM4_CH3{slash}EVENTOUT-Pad85)") (class "Default")
      (node (ref "MDE_STM32F407Z") (pin "85") (pinfunction "PD14/FSMC_D0/TIM4_CH3/EVENTOUT_85") (pintype "passive"))
    )
    (net (code "82") (name "unconnected-(MDE_STM32F407Z-PD15{slash}FSMC_D1{slash}TIM4_CH4{slash}EVENTOUT-Pad86)") (class "Default")
      (node (ref "MDE_STM32F407Z") (pin "86") (pinfunction "PD15/FSMC_D1/TIM4_CH4/EVENTOUT_86") (pintype "passive"))
    )
    (net (code "83") (name "unconnected-(MDE_STM32F407Z-PE0{slash}TIM4_ETR{slash}FSMC_NBL0{slash}DCMI_D2{slash}EVENTOUT-Pad141)") (class "Default")
      (node (ref "MDE_STM32F407Z") (pin "141") (pinfunction "PE0/TIM4_ETR/FSMC_NBL0/DCMI_D2/EVENTOUT_141") (pintype "passive"))
    )
    (net (code "84") (name "unconnected-(MDE_STM32F407Z-PE1{slash}FSMC_NBL1{slash}DCMI_D3{slash}EVENTOUT-Pad142)") (class "Default")
      (node (ref "MDE_STM32F407Z") (pin "142") (pinfunction "PE1/FSMC_NBL1/DCMI_D3/EVENTOUT_142") (pintype "passive"))
    )
    (net (code "85") (name "unconnected-(MDE_STM32F407Z-PE2{slash}TRACECLK{slash}FSMC_A23{slash}ETH_MII_TXD3{slash}EVENTOUT-Pad1)") (class "Default")
      (node (ref "MDE_STM32F407Z") (pin "1") (pinfunction "PE2/TRACECLK/FSMC_A23/ETH_MII_TXD3/EVENTOUT_1") (pintype "passive"))
    )
    (net (code "86") (name "unconnected-(MDE_STM32F407Z-PE3{slash}TRACED0{slash}FSMC_A19{slash}EVENTOUT-Pad2)") (class "Default")
      (node (ref "MDE_STM32F407Z") (pin "2") (pinfunction "PE3/TRACED0/FSMC_A19/EVENTOUT_2") (pintype "passive"))
    )
    (net (code "87") (name "unconnected-(MDE_STM32F407Z-PE4{slash}TRACED1{slash}FSMC_A20{slash}DCMI_D4{slash}EVENT_OUT-Pad3)") (class "Default")
      (node (ref "MDE_STM32F407Z") (pin "3") (pinfunction "PE4/TRACED1/FSMC_A20/DCMI_D4/EVENT_OUT_3") (pintype "passive"))
    )
    (net (code "88") (name "unconnected-(MDE_STM32F407Z-PE5{slash}TRACED2{slash}FSMC_A21{slash}TIM9_CH1{slash}DCMI_D6{slash}EVENTOUT-Pad4)") (class "Default")
      (node (ref "MDE_STM32F407Z") (pin "4") (pinfunction "PE5/TRACED2/FSMC_A21/TIM9_CH1/DCMI_D6/EVENTOUT_4") (pintype "passive"))
    )
    (net (code "89") (name "unconnected-(MDE_STM32F407Z-PE6{slash}TRACED3{slash}FSMC_A22{slash}TIM9_CH2{slash}DCMI_D7{slash}EVENTOUT-Pad5)") (class "Default")
      (node (ref "MDE_STM32F407Z") (pin "5") (pinfunction "PE6/TRACED3/FSMC_A22/TIM9_CH2/DCMI_D7/EVENTOUT_5") (pintype "passive"))
    )
    (net (code "90") (name "unconnected-(MDE_STM32F407Z-PE7{slash}FSMC_D4{slash}TIM1_ETR{slash}EVENTOUT-Pad58)") (class "Default")
      (node (ref "MDE_STM32F407Z") (pin "58") (pinfunction "PE7/FSMC_D4/TIM1_ETR/EVENTOUT_58") (pintype "passive"))
    )
    (net (code "91") (name "unconnected-(MDE_STM32F407Z-PF0{slash}FSMC_A0{slash}I2C2_SDA{slash}EVENTOUT-Pad10)") (class "Default")
      (node (ref "MDE_STM32F407Z") (pin "10") (pinfunction "PF0/FSMC_A0/I2C2_SDA/EVENTOUT_10") (pintype "passive"))
    )
    (net (code "92") (name "unconnected-(MDE_STM32F407Z-PF1{slash}FSMC_A1{slash}I2C2_SCL{slash}EVENTOUT-Pad11)") (class "Default")
      (node (ref "MDE_STM32F407Z") (pin "11") (pinfunction "PF1/FSMC_A1/I2C2_SCL/EVENTOUT_11") (pintype "passive"))
    )
    (net (code "93") (name "unconnected-(MDE_STM32F407Z-PF2{slash}FSMC_A2{slash}I2C2_SMBA{slash}EVENTOUT-Pad12)") (class "Default")
      (node (ref "MDE_STM32F407Z") (pin "12") (pinfunction "PF2/FSMC_A2/I2C2_SMBA/EVENTOUT_12") (pintype "passive"))
    )
    (net (code "94") (name "unconnected-(MDE_STM32F407Z-PF3{slash}FSMC_A3{slash}EVENTOUT{slash}ADC3_IN9-Pad13)") (class "Default")
      (node (ref "MDE_STM32F407Z") (pin "13") (pinfunction "PF3/FSMC_A3/EVENTOUT/ADC3_IN9_13") (pintype "passive"))
    )
    (net (code "95") (name "unconnected-(MDE_STM32F407Z-PF4{slash}FSMC_A4{slash}EVNETOUT{slash}ADC3_IN14-Pad14)") (class "Default")
      (node (ref "MDE_STM32F407Z") (pin "14") (pinfunction "PF4/FSMC_A4/EVNETOUT/ADC3_IN14_14") (pintype "passive"))
    )
    (net (code "96") (name "unconnected-(MDE_STM32F407Z-PF5{slash}FSMC_A5{slash}EVENTOUT{slash}ADC3_IN15-Pad15)") (class "Default")
      (node (ref "MDE_STM32F407Z") (pin "15") (pinfunction "PF5/FSMC_A5/EVENTOUT/ADC3_IN15_15") (pintype "passive"))
    )
    (net (code "97") (name "unconnected-(MDE_STM32F407Z-PF6{slash}TIM10_CH1{slash}FSMC_NIORD{slash}EVENTOUT{slash}ADC3_IN4-Pad18)") (class "Default")
      (node (ref "MDE_STM32F407Z") (pin "18") (pinfunction "PF6/TIM10_CH1/FSMC_NIORD/EVENTOUT/ADC3_IN4_18") (pintype "passive"))
    )
    (net (code "98") (name "unconnected-(MDE_STM32F407Z-PF7{slash}TIM11_CH1{slash}FSMC_NREG{slash}EVENTOUT{slash}ADC3_IN5-Pad19)") (class "Default")
      (node (ref "MDE_STM32F407Z") (pin "19") (pinfunction "PF7/TIM11_CH1/FSMC_NREG/EVENTOUT/ADC3_IN5_19") (pintype "passive"))
    )
    (net (code "99") (name "unconnected-(MDE_STM32F407Z-PF8{slash}TIM13_CH1{slash}FSMC_NIOWR{slash}EVENTOUT{slash}ADC3_IN6-Pad20)") (class "Default")
      (node (ref "MDE_STM32F407Z") (pin "20") (pinfunction "PF8/TIM13_CH1/FSMC_NIOWR/EVENTOUT/ADC3_IN6_20") (pintype "passive"))
    )
    (net (code "100") (name "unconnected-(MDE_STM32F407Z-PF9{slash}TIM14_CH1{slash}FSMC_CD{slash}EVENTOUT{slash}ADC3_IN7-Pad21)") (class "Default")
      (node (ref "MDE_STM32F407Z") (pin "21") (pinfunction "PF9/TIM14_CH1/FSMC_CD/EVENTOUT/ADC3_IN7_21") (pintype "passive"))
    )
    (net (code "101") (name "unconnected-(MDE_STM32F407Z-PF11{slash}DCMI_12{slash}EVENTOUT-Pad49)") (class "Default")
      (node (ref "MDE_STM32F407Z") (pin "49") (pinfunction "PF11/DCMI_12/EVENTOUT_49") (pintype "passive"))
    )
    (net (code "102") (name "unconnected-(MDE_STM32F407Z-PF12{slash}FSMC_A6{slash}EVENTOUT-Pad50)") (class "Default")
      (node (ref "MDE_STM32F407Z") (pin "50") (pinfunction "PF12/FSMC_A6/EVENTOUT_50") (pintype "passive"))
    )
    (net (code "103") (name "unconnected-(MDE_STM32F407Z-PF13{slash}FSMC_A7{slash}EVENTOUT-Pad53)") (class "Default")
      (node (ref "MDE_STM32F407Z") (pin "53") (pinfunction "PF13/FSMC_A7/EVENTOUT_53") (pintype "passive"))
    )
    (net (code "104") (name "unconnected-(MDE_STM32F407Z-PF14{slash}FSMC_A8{slash}EVENTOUT-Pad54)") (class "Default")
      (node (ref "MDE_STM32F407Z") (pin "54") (pinfunction "PF14/FSMC_A8/EVENTOUT_54") (pintype "passive"))
    )
    (net (code "105") (name "unconnected-(MDE_STM32F407Z-PF15{slash}FSMC_A9{slash}EVENTOUT-Pad55)") (class "Default")
      (node (ref "MDE_STM32F407Z") (pin "55") (pinfunction "PF15/FSMC_A9/EVENTOUT_55") (pintype "passive"))
    )
    (net (code "106") (name "unconnected-(MDE_STM32F407Z-PG0{slash}FSMC_A10{slash}EVENTOUT-Pad56)") (class "Default")
      (node (ref "MDE_STM32F407Z") (pin "56") (pinfunction "PG0/FSMC_A10/EVENTOUT_56") (pintype "passive"))
    )
    (net (code "107") (name "unconnected-(MDE_STM32F407Z-PG1{slash}FSMC_A11{slash}EVENTOUT-Pad57)") (class "Default")
      (node (ref "MDE_STM32F407Z") (pin "57") (pinfunction "PG1/FSMC_A11/EVENTOUT_57") (pintype "passive"))
    )
    (net (code "108") (name "unconnected-(MDE_STM32F407Z-PG2{slash}FSMC_A12{slash}EVENTOUT-Pad87)") (class "Default")
      (node (ref "MDE_STM32F407Z") (pin "87") (pinfunction "PG2/FSMC_A12/EVENTOUT_87") (pintype "passive"))
    )
    (net (code "109") (name "unconnected-(MDE_STM32F407Z-PG3{slash}FSMC_A13{slash}EVENTOUT-Pad88)") (class "Default")
      (node (ref "MDE_STM32F407Z") (pin "88") (pinfunction "PG3/FSMC_A13/EVENTOUT_88") (pintype "passive"))
    )
    (net (code "110") (name "unconnected-(MDE_STM32F407Z-PG4{slash}FSMC_A14{slash}EVENTOUT-Pad89)") (class "Default")
      (node (ref "MDE_STM32F407Z") (pin "89") (pinfunction "PG4/FSMC_A14/EVENTOUT_89") (pintype "passive"))
    )
    (net (code "111") (name "unconnected-(MDE_STM32F407Z-PG5{slash}FSMC_A15{slash}EVENTOUT-Pad90)") (class "Default")
      (node (ref "MDE_STM32F407Z") (pin "90") (pinfunction "PG5/FSMC_A15/EVENTOUT_90") (pintype "passive"))
    )
    (net (code "112") (name "unconnected-(MDE_STM32F407Z-PG6{slash}FSMC_INT2{slash}EVENTOUT-Pad91)") (class "Default")
      (node (ref "MDE_STM32F407Z") (pin "91") (pinfunction "PG6/FSMC_INT2/EVENTOUT_91") (pintype "passive"))
    )
    (net (code "113") (name "unconnected-(MDE_STM32F407Z-PG7{slash}FSMC_INT3{slash}USART6_CK{slash}EVENTOUT-Pad92)") (class "Default")
      (node (ref "MDE_STM32F407Z") (pin "92") (pinfunction "PG7/FSMC_INT3/USART6_CK/EVENTOUT_92") (pintype "passive"))
    )
    (net (code "114") (name "unconnected-(MDE_STM32F407Z-SPI3_SCK{slash}I2S3_CK{slash}USART4_TX{slash}SDIO_D2{slash}DCMI_D8{slash}USART3_TX{slash}EVENTOUT{slash}PC10{slash}SDUsed-Pad111)") (class "Default")
      (node (ref "MDE_STM32F407Z") (pin "111") (pinfunction "SPI3_SCK/I2S3_CK/USART4_TX/SDIO_D2/DCMI_D8/USART3_TX/EVENTOUT/PC10/SDUsed_111") (pintype "passive"))
    )
    (net (code "115") (name "unconnected-(MDE_STM32F407Z-TIM3_ETR{slash}UART5_RX{slash}SDIO_CMD{slash}DCMI_D11{slash}EVENTOUT{slash}PD2{slash}SDUsed-Pad116)") (class "Default")
      (node (ref "MDE_STM32F407Z") (pin "116") (pinfunction "TIM3_ETR/UART5_RX/SDIO_CMD/DCMI_D11/EVENTOUT/PD2/SDUsed_116") (pintype "passive"))
    )
    (net (code "116") (name "unconnected-(MDE_STM32F407Z-UART5_TX{slash}SDIO_CK{slash}DCMI_D9{slash}SPI3_MOSI{slash}I2S3_SD{slash}USART3_CK{slash}EVENTOUT{slash}PC12{slash}SDUsed-Pad113)") (class "Default")
      (node (ref "MDE_STM32F407Z") (pin "113") (pinfunction "UART5_TX/SDIO_CK/DCMI_D9/SPI3_MOSI/I2S3_SD/USART3_CK/EVENTOUT/PC12/SDUsed_113") (pintype "passive"))
    )
    (net (code "117") (name "unconnected-(MDE_STM32F407Z-USART1_CTS{slash}CAN1_RX{slash}TIM1_CH4{slash}OTG_FS_DM{slash}EVENTOUT{slash}PA11{slash}USBUsed-Pad103)") (class "Default")
      (node (ref "MDE_STM32F407Z") (pin "103") (pinfunction "USART1_CTS/CAN1_RX/TIM1_CH4/OTG_FS_DM/EVENTOUT/PA11/USBUsed_103") (pintype "passive"))
    )
    (net (code "118") (name "unconnected-(MDE_STM32F407Z-USART1_RTS{slash}CAN1_TX{slash}TIM1_ETR{slash}OTG_FS_DP{slash}EVENTOUT{slash}PA12{slash}USBUsed-Pad104)") (class "Default")
      (node (ref "MDE_STM32F407Z") (pin "104") (pinfunction "USART1_RTS/CAN1_TX/TIM1_ETR/OTG_FS_DP/EVENTOUT/PA12/USBUsed_104") (pintype "passive"))
    )
    (net (code "119") (name "unconnected-(MDE_STM32F407Z-USART4_RX{slash}SPI3_MISO{slash}SDIO_D3{slash}DCMI_D4{slash}USART3_RX{slash}I2S3ext_SD{slash}EVENTOUT{slash}PC11{slash}SDUsed-Pad112)") (class "Default")
      (node (ref "MDE_STM32F407Z") (pin "112") (pinfunction "USART4_RX/SPI3_MISO/SDIO_D3/DCMI_D4/USART3_RX/I2S3ext_SD/EVENTOUT/PC11/SDUsed_112") (pintype "passive"))
    )
    (net (code "120") (name "unconnected-(MDE_STM32F407Z-USART6_CTS{slash}DCMI_D13{slash}EVENTOUT{slash}PG15{slash}Used-Pad132)") (class "Default")
      (node (ref "MDE_STM32F407Z") (pin "132") (pinfunction "USART6_CTS/DCMI_D13/EVENTOUT/PG15/Used_132") (pintype "passive"))
    )
    (net (code "121") (name "unconnected-(MDE_STM32F407Z-USART6_RTS{slash}ETH_PPS_OUT{slash}EVENTOUT{slash}PG8-Pad93)") (class "Default")
      (node (ref "MDE_STM32F407Z") (pin "93") (pinfunction "USART6_RTS/ETH_PPS_OUT/EVENTOUT/PG8_93") (pintype "passive"))
    )
    (net (code "122") (name "unconnected-(MDE_STM32F407Z-Used{slash}PB2-BOOT1{slash}EVENTOUT-Pad48)") (class "Default")
      (node (ref "MDE_STM32F407Z") (pin "48") (pinfunction "Used/PB2-BOOT1/EVENTOUT_48") (pintype "passive"))
    )
    (net (code "123") (name "unconnected-(MDE_STM32F407Z-Used{slash}PB12{slash}SPI2_NSS{slash}I2S2_WS{slash}I2C2_SMBA{slash}USART3_CK{slash}TIM1_BKIN{slash}CAN2_RX{slash}OTG_HS_ULPI_D5{slash}ETH_RMII_TXD0{slash}ETH_MII_TXD0{slash}OTG_HS_ID{slash}EVENTOUT-Pad73)") (class "Default")
      (node (ref "MDE_STM32F407Z") (pin "73") (pinfunction "Used/PB12/SPI2_NSS/I2S2_WS/I2C2_SMBA/USART3_CK/TIM1_BKIN/CAN2_RX/OTG_HS_ULPI_D5/ETH_RMII_TXD0/ETH_MII_TXD0/OTG_HS_ID/EVENTOUT_73") (pintype "passive"))
    )
    (net (code "124") (name "unconnected-(MDE_STM32F407Z-Used{slash}PC14-OSC32_IN{slash}EVENTOUT-Pad8)") (class "Default")
      (node (ref "MDE_STM32F407Z") (pin "8") (pinfunction "Used/PC14-OSC32_IN/EVENTOUT_8") (pintype "passive"))
    )
    (net (code "125") (name "unconnected-(MDE_STM32F407Z-Used{slash}PC15-OSC32_OUT{slash}EVENTOUT-Pad9)") (class "Default")
      (node (ref "MDE_STM32F407Z") (pin "9") (pinfunction "Used/PC15-OSC32_OUT/EVENTOUT_9") (pintype "passive"))
    )
    (net (code "126") (name "unconnected-(MDE_STM32F407Z-Used{slash}PF10{slash}FSMC_INTR{slash}EVENTOUT{slash}ADC3_IN8-Pad22)") (class "Default")
      (node (ref "MDE_STM32F407Z") (pin "22") (pinfunction "Used/PF10/FSMC_INTR/EVENTOUT/ADC3_IN8_22") (pintype "passive"))
    )
    (net (code "127") (name "unconnected-(MDE_STM32F407Z-VCC3.3V_Out_1-Pad202)") (class "Default")
      (node (ref "MDE_STM32F407Z") (pin "202") (pinfunction "VCC3.3V_Out_1_202") (pintype "passive"))
    )
    (net (code "128") (name "unconnected-(MDE_STM32F407Z-VCC3.3V_Out_2-Pad203)") (class "Default")
      (node (ref "MDE_STM32F407Z") (pin "203") (pinfunction "VCC3.3V_Out_2_203") (pintype "passive"))
    )
    (net (code "129") (name "unconnected-(MDE_STM32F407Z-VCC3.3V_Out_3-Pad207)") (class "Default")
      (node (ref "MDE_STM32F407Z") (pin "207") (pinfunction "VCC3.3V_Out_3_207") (pintype "passive"))
    )
    (net (code "130") (name "unconnected-(SWD-VCC3.3V-Pad1)") (class "Default")
      (node (ref "SWD") (pin "1") (pinfunction "VCC3.3V_1") (pintype "passive"))
    )
  )
)
